# Clock_Updated_3_Nets.net
KiCad netlist of a schematic drawn in EAGLE
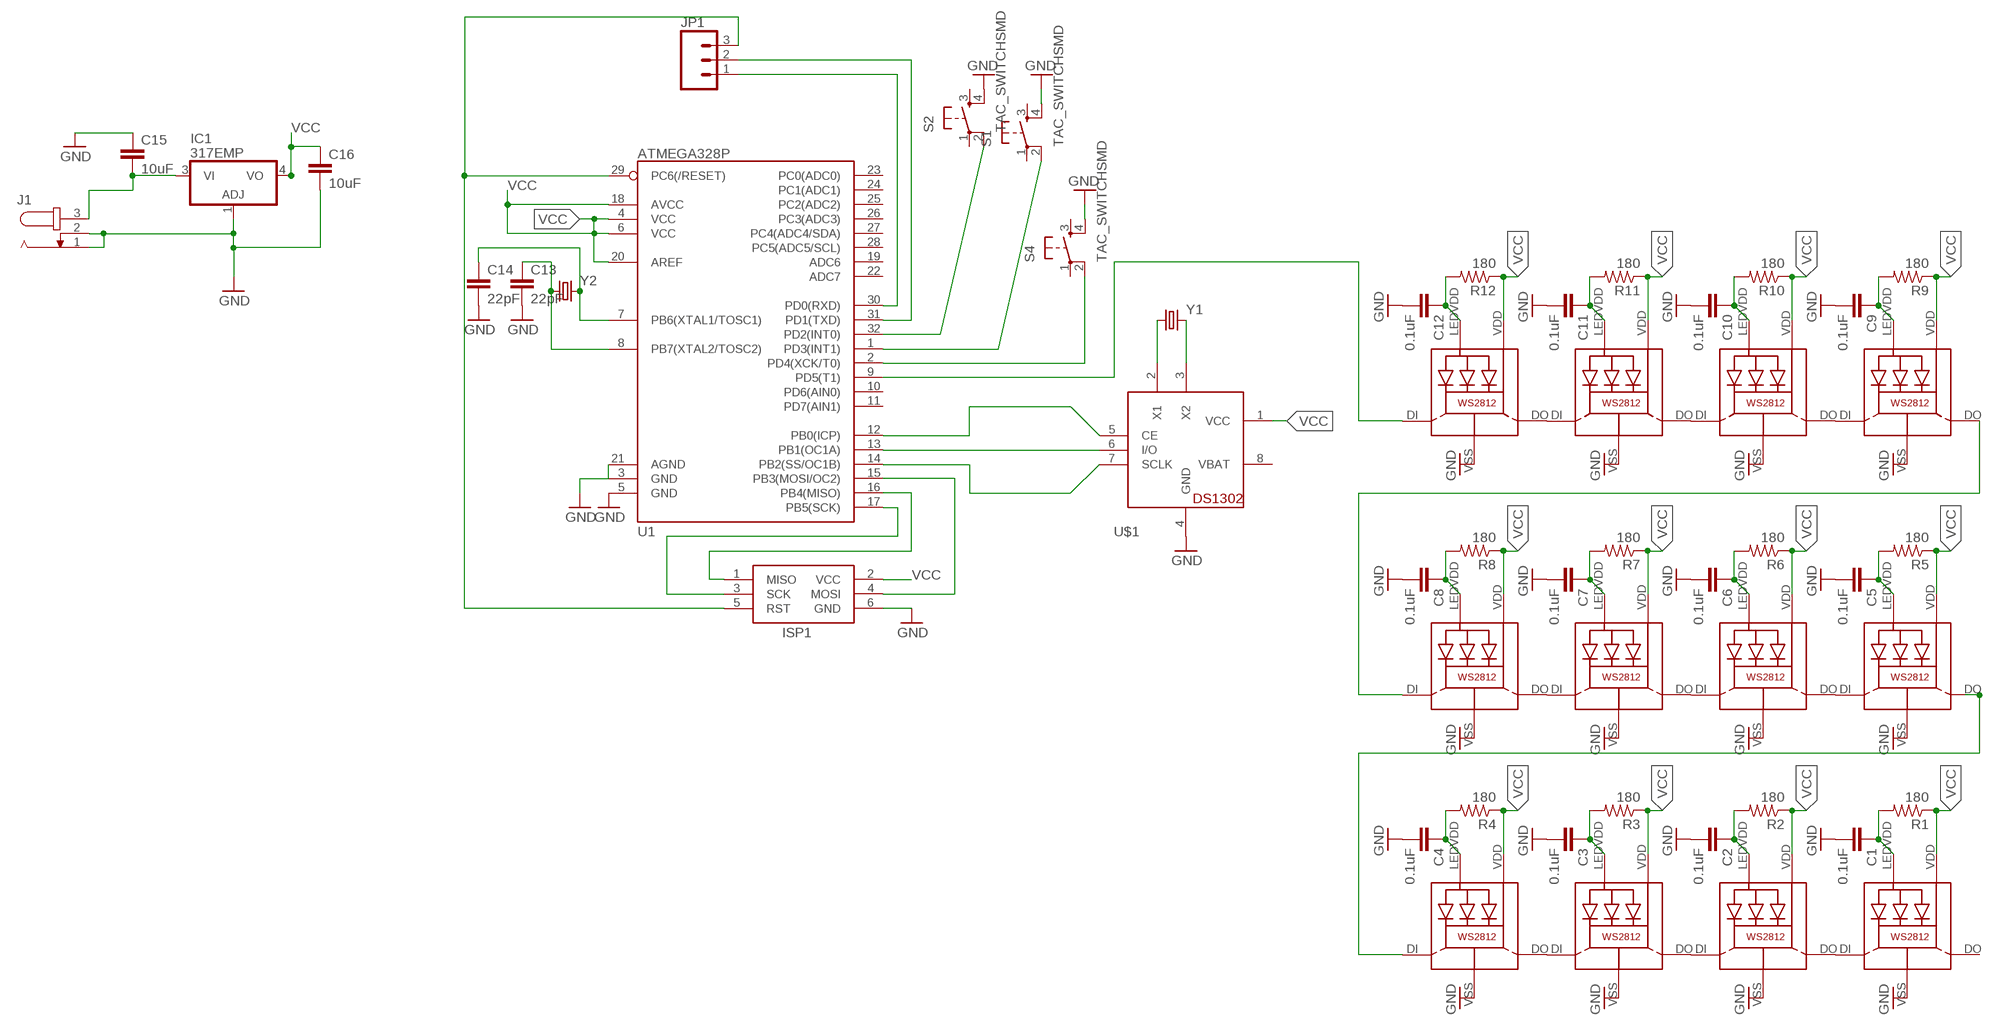
[diagram p0: schematic, sheet 1]

(export (version "E")
  (design (tool "Eeschema 10.0.6"))
  (components
    (comp (ref "C1")
      (value "0.1uF")
      (footprint "eagle-import:0603-CAP")
      (libsource (lib "eagle-import") (part "0.1UF-25V(+80/-20%)(0603)"))
    )
    (comp (ref "C2")
      (value "0.1uF")
      (footprint "eagle-import:0603-CAP")
      (libsource (lib "eagle-import") (part "0.1UF-25V(+80/-20%)(0603)"))
    )
    (comp (ref "C3")
      (value "0.1uF")
      (footprint "eagle-import:0603-CAP")
      (libsource (lib "eagle-import") (part "0.1UF-25V(+80/-20%)(0603)"))
    )
    (comp (ref "C4")
      (value "0.1uF")
      (footprint "eagle-import:0603-CAP")
      (libsource (lib "eagle-import") (part "0.1UF-25V(+80/-20%)(0603)"))
    )
    (comp (ref "C5")
      (value "0.1uF")
      (footprint "eagle-import:0603-CAP")
      (libsource (lib "eagle-import") (part "0.1UF-25V(+80/-20%)(0603)"))
    )
    (comp (ref "C6")
      (value "0.1uF")
      (footprint "eagle-import:0603-CAP")
      (libsource (lib "eagle-import") (part "0.1UF-25V(+80/-20%)(0603)"))
    )
    (comp (ref "C7")
      (value "0.1uF")
      (footprint "eagle-import:0603-CAP")
      (libsource (lib "eagle-import") (part "0.1UF-25V(+80/-20%)(0603)"))
    )
    (comp (ref "C8")
      (value "0.1uF")
      (footprint "eagle-import:0603-CAP")
      (libsource (lib "eagle-import") (part "0.1UF-25V(+80/-20%)(0603)"))
    )
    (comp (ref "C9")
      (value "0.1uF")
      (footprint "eagle-import:0603-CAP")
      (libsource (lib "eagle-import") (part "0.1UF-25V(+80/-20%)(0603)"))
    )
    (comp (ref "C10")
      (value "0.1uF")
      (footprint "eagle-import:0603-CAP")
      (libsource (lib "eagle-import") (part "0.1UF-25V(+80/-20%)(0603)"))
    )
    (comp (ref "C11")
      (value "0.1uF")
      (footprint "eagle-import:0603-CAP")
      (libsource (lib "eagle-import") (part "0.1UF-25V(+80/-20%)(0603)"))
    )
    (comp (ref "C12")
      (value "0.1uF")
      (footprint "eagle-import:0603-CAP")
      (libsource (lib "eagle-import") (part "0.1UF-25V(+80/-20%)(0603)"))
    )
    (comp (ref "C13")
      (value "22pF")
      (footprint "eagle-import:0603-CAP")
      (libsource (lib "eagle-import") (part "22PF-50V-5%(0603)"))
    )
    (comp (ref "C14")
      (value "22pF")
      (footprint "eagle-import:0603-CAP")
      (libsource (lib "eagle-import") (part "22PF-50V-5%(0603)"))
    )
    (comp (ref "C15")
      (value "10uF")
      (footprint "eagle-import:1206")
      (libsource (lib "eagle-import") (part "10UF-6.3V-20%(1206)"))
    )
    (comp (ref "C16")
      (value "10uF")
      (footprint "eagle-import:1206")
      (libsource (lib "eagle-import") (part "10UF-6.3V-20%(1206)"))
    )
    (comp (ref "IC1")
      (value "317EMP")
      (footprint "eagle-import:SOT223")
      (libsource (lib "eagle-import") (part "317EMP"))
    )
    (comp (ref "ISP1")
      (value "AVRISP-6")
      (footprint "eagle-import:AVRISP")
      (libsource (lib "eagle-import") (part "AVRISP-6"))
    )
    (comp (ref "J1")
      (value "JACK-PLUG0")
      (footprint "eagle-import:SPC4077")
      (libsource (lib "eagle-import") (part "JACK-PLUG0"))
    )
    (comp (ref "JP1")
      (value "M03JST-PTH-VERT")
      (footprint "eagle-import:JST-3-PTH-VERT")
      (libsource (lib "eagle-import") (part "M03JST-PTH-VERT"))
    )
    (comp (ref "LED1")
      (value "WS2812")
      (footprint "eagle-import:WS2812")
      (libsource (lib "eagle-import") (part "WS2812"))
    )
    (comp (ref "LED2")
      (value "WS2812")
      (footprint "eagle-import:WS2812")
      (libsource (lib "eagle-import") (part "WS2812"))
    )
    (comp (ref "LED3")
      (value "WS2812")
      (footprint "eagle-import:WS2812")
      (libsource (lib "eagle-import") (part "WS2812"))
    )
    (comp (ref "LED4")
      (value "WS2812")
      (footprint "eagle-import:WS2812")
      (libsource (lib "eagle-import") (part "WS2812"))
    )
    (comp (ref "LED5")
      (value "WS2812")
      (footprint "eagle-import:WS2812")
      (libsource (lib "eagle-import") (part "WS2812"))
    )
    (comp (ref "LED6")
      (value "WS2812")
      (footprint "eagle-import:WS2812")
      (libsource (lib "eagle-import") (part "WS2812"))
    )
    (comp (ref "LED7")
      (value "WS2812")
      (footprint "eagle-import:WS2812")
      (libsource (lib "eagle-import") (part "WS2812"))
    )
    (comp (ref "LED8")
      (value "WS2812")
      (footprint "eagle-import:WS2812")
      (libsource (lib "eagle-import") (part "WS2812"))
    )
    (comp (ref "LED9")
      (value "WS2812")
      (footprint "eagle-import:WS2812")
      (libsource (lib "eagle-import") (part "WS2812"))
    )
    (comp (ref "LED10")
      (value "WS2812")
      (footprint "eagle-import:WS2812")
      (libsource (lib "eagle-import") (part "WS2812"))
    )
    (comp (ref "LED11")
      (value "WS2812")
      (footprint "eagle-import:WS2812")
      (libsource (lib "eagle-import") (part "WS2812"))
    )
    (comp (ref "LED12")
      (value "WS2812")
      (footprint "eagle-import:WS2812")
      (libsource (lib "eagle-import") (part "WS2812"))
    )
    (comp (ref "R1")
      (value "180")
      (footprint "eagle-import:0603-RES")
      (libsource (lib "eagle-import") (part "180OHM1/10W1%(0603)"))
    )
    (comp (ref "R2")
      (value "180")
      (footprint "eagle-import:0603-RES")
      (libsource (lib "eagle-import") (part "180OHM1/10W1%(0603)"))
    )
    (comp (ref "R3")
      (value "180")
      (footprint "eagle-import:0603-RES")
      (libsource (lib "eagle-import") (part "180OHM1/10W1%(0603)"))
    )
    (comp (ref "R4")
      (value "180")
      (footprint "eagle-import:0603-RES")
      (libsource (lib "eagle-import") (part "180OHM1/10W1%(0603)"))
    )
    (comp (ref "R5")
      (value "180")
      (footprint "eagle-import:0603-RES")
      (libsource (lib "eagle-import") (part "180OHM1/10W1%(0603)"))
    )
    (comp (ref "R6")
      (value "180")
      (footprint "eagle-import:0603-RES")
      (libsource (lib "eagle-import") (part "180OHM1/10W1%(0603)"))
    )
    (comp (ref "R7")
      (value "180")
      (footprint "eagle-import:0603-RES")
      (libsource (lib "eagle-import") (part "180OHM1/10W1%(0603)"))
    )
    (comp (ref "R8")
      (value "180")
      (footprint "eagle-import:0603-RES")
      (libsource (lib "eagle-import") (part "180OHM1/10W1%(0603)"))
    )
    (comp (ref "R9")
      (value "180")
      (footprint "eagle-import:0603-RES")
      (libsource (lib "eagle-import") (part "180OHM1/10W1%(0603)"))
    )
    (comp (ref "R10")
      (value "180")
      (footprint "eagle-import:0603-RES")
      (libsource (lib "eagle-import") (part "180OHM1/10W1%(0603)"))
    )
    (comp (ref "R11")
      (value "180")
      (footprint "eagle-import:0603-RES")
      (libsource (lib "eagle-import") (part "180OHM1/10W1%(0603)"))
    )
    (comp (ref "R12")
      (value "180")
      (footprint "eagle-import:0603-RES")
      (libsource (lib "eagle-import") (part "180OHM1/10W1%(0603)"))
    )
    (comp (ref "S1")
      (value "TAC_SWITCHSMD")
      (footprint "eagle-import:TACTILE-SWITCH-SMD")
      (libsource (lib "eagle-import") (part "TAC_SWITCHSMD"))
    )
    (comp (ref "S2")
      (value "TAC_SWITCHSMD")
      (footprint "eagle-import:TACTILE-SWITCH-SMD")
      (libsource (lib "eagle-import") (part "TAC_SWITCHSMD"))
    )
    (comp (ref "S4")
      (value "TAC_SWITCHSMD")
      (footprint "eagle-import:TACTILE-SWITCH-SMD")
      (libsource (lib "eagle-import") (part "TAC_SWITCHSMD"))
    )
    (comp (ref "U$1")
      (value "DS1302")
      (footprint "eagle-import:DIL08-ROUND")
      (libsource (lib "eagle-import") (part "DS1302"))
    )
    (comp (ref "U1")
      (value "ATMEGA328P")
      (footprint "eagle-import:TQFP32-08")
      (libsource (lib "eagle-import") (part "ATMEGA328_SMT"))
    )
    (comp (ref "Y1")
      (value "CRYSTALTC38H")
      (footprint "eagle-import:TC38H")
      (libsource (lib "eagle-import") (part "CRYSTALTC38H"))
    )
    (comp (ref "Y2")
      (value "CRYSTALSMD")
      (footprint "eagle-import:HC49UP")
      (libsource (lib "eagle-import") (part "CRYSTALSMD"))
    )
  )
  (nets
    (net (code "1") (name "/VBAT") (class "Default")
      (node (ref "U$1") (pin "8") (pinfunction "VBAT_8") (pintype "power_in"))
    )
    (net (code "2") (name "GND") (class "Default")
      (node (ref "C1") (pin "2") (pinfunction "2_2") (pintype "passive"))
      (node (ref "C10") (pin "2") (pinfunction "2_2") (pintype "passive"))
      (node (ref "C11") (pin "2") (pinfunction "2_2") (pintype "passive"))
      (node (ref "C12") (pin "2") (pinfunction "2_2") (pintype "passive"))
      (node (ref "C13") (pin "2") (pinfunction "2_2") (pintype "passive"))
      (node (ref "C14") (pin "2") (pinfunction "2_2") (pintype "passive"))
      (node (ref "C15") (pin "1") (pinfunction "1_1") (pintype "passive"))
      (node (ref "C16") (pin "2") (pinfunction "2_2") (pintype "passive"))
      (node (ref "C2") (pin "2") (pinfunction "2_2") (pintype "passive"))
      (node (ref "C3") (pin "2") (pinfunction "2_2") (pintype "passive"))
      (node (ref "C4") (pin "2") (pinfunction "2_2") (pintype "passive"))
      (node (ref "C5") (pin "2") (pinfunction "2_2") (pintype "passive"))
      (node (ref "C6") (pin "2") (pinfunction "2_2") (pintype "passive"))
      (node (ref "C7") (pin "2") (pinfunction "2_2") (pintype "passive"))
      (node (ref "C8") (pin "2") (pinfunction "2_2") (pintype "passive"))
      (node (ref "C9") (pin "2") (pinfunction "2_2") (pintype "passive"))
      (node (ref "IC1") (pin "1") (pinfunction "ADJ_1") (pintype "input"))
      (node (ref "ISP1") (pin "6") (pinfunction "GND_6") (pintype "power_in"))
      (node (ref "J1") (pin "1") (pinfunction "1_1") (pintype "passive"))
      (node (ref "J1") (pin "2") (pinfunction "2_2") (pintype "passive"))
      (node (ref "LED1") (pin "VSS") (pinfunction "GND_VSS") (pintype "power_in"))
      (node (ref "LED10") (pin "VSS") (pinfunction "GND_VSS") (pintype "power_in"))
      (node (ref "LED11") (pin "VSS") (pinfunction "GND_VSS") (pintype "power_in"))
      (node (ref "LED12") (pin "VSS") (pinfunction "GND_VSS") (pintype "power_in"))
      (node (ref "LED2") (pin "VSS") (pinfunction "GND_VSS") (pintype "power_in"))
      (node (ref "LED3") (pin "VSS") (pinfunction "GND_VSS") (pintype "power_in"))
      (node (ref "LED4") (pin "VSS") (pinfunction "GND_VSS") (pintype "power_in"))
      (node (ref "LED5") (pin "VSS") (pinfunction "GND_VSS") (pintype "power_in"))
      (node (ref "LED6") (pin "VSS") (pinfunction "GND_VSS") (pintype "power_in"))
      (node (ref "LED7") (pin "VSS") (pinfunction "GND_VSS") (pintype "power_in"))
      (node (ref "LED8") (pin "VSS") (pinfunction "GND_VSS") (pintype "power_in"))
      (node (ref "LED9") (pin "VSS") (pinfunction "GND_VSS") (pintype "power_in"))
      (node (ref "S1") (pin "4") (pinfunction "4_4") (pintype "passive"))
      (node (ref "S2") (pin "4") (pinfunction "4_4") (pintype "passive"))
      (node (ref "S4") (pin "4") (pinfunction "4_4") (pintype "passive"))
      (node (ref "U$1") (pin "4") (pinfunction "GND_4") (pintype "power_in"))
      (node (ref "U1") (pin "21") (pinfunction "AGND_21") (pintype "bidirectional"))
      (node (ref "U1") (pin "3") (pinfunction "GND_3") (pintype "bidirectional"))
      (node (ref "U1") (pin "5") (pinfunction "GND_5") (pintype "bidirectional"))
    )
    (net (code "3") (name "Net-(C1-Pad1)") (class "Default")
      (node (ref "C1") (pin "1") (pinfunction "1_1") (pintype "passive"))
      (node (ref "LED1") (pin "LEDVDD") (pinfunction "LEDVDD_LEDVDD") (pintype "power_in"))
      (node (ref "R1") (pin "2") (pinfunction "2_2") (pintype "passive"))
    )
    (net (code "4") (name "Net-(C2-Pad1)") (class "Default")
      (node (ref "C2") (pin "1") (pinfunction "1_1") (pintype "passive"))
      (node (ref "LED2") (pin "LEDVDD") (pinfunction "LEDVDD_LEDVDD") (pintype "power_in"))
      (node (ref "R2") (pin "2") (pinfunction "2_2") (pintype "passive"))
    )
    (net (code "5") (name "Net-(C3-Pad1)") (class "Default")
      (node (ref "C3") (pin "1") (pinfunction "1_1") (pintype "passive"))
      (node (ref "LED3") (pin "LEDVDD") (pinfunction "LEDVDD_LEDVDD") (pintype "power_in"))
      (node (ref "R3") (pin "2") (pinfunction "2_2") (pintype "passive"))
    )
    (net (code "6") (name "Net-(C4-Pad1)") (class "Default")
      (node (ref "C4") (pin "1") (pinfunction "1_1") (pintype "passive"))
      (node (ref "LED4") (pin "LEDVDD") (pinfunction "LEDVDD_LEDVDD") (pintype "power_in"))
      (node (ref "R4") (pin "2") (pinfunction "2_2") (pintype "passive"))
    )
    (net (code "7") (name "Net-(C5-Pad1)") (class "Default")
      (node (ref "C5") (pin "1") (pinfunction "1_1") (pintype "passive"))
      (node (ref "LED5") (pin "LEDVDD") (pinfunction "LEDVDD_LEDVDD") (pintype "power_in"))
      (node (ref "R5") (pin "2") (pinfunction "2_2") (pintype "passive"))
    )
    (net (code "8") (name "Net-(C6-Pad1)") (class "Default")
      (node (ref "C6") (pin "1") (pinfunction "1_1") (pintype "passive"))
      (node (ref "LED6") (pin "LEDVDD") (pinfunction "LEDVDD_LEDVDD") (pintype "power_in"))
      (node (ref "R6") (pin "2") (pinfunction "2_2") (pintype "passive"))
    )
    (net (code "9") (name "Net-(C7-Pad1)") (class "Default")
      (node (ref "C7") (pin "1") (pinfunction "1_1") (pintype "passive"))
      (node (ref "LED7") (pin "LEDVDD") (pinfunction "LEDVDD_LEDVDD") (pintype "power_in"))
      (node (ref "R7") (pin "2") (pinfunction "2_2") (pintype "passive"))
    )
    (net (code "10") (name "Net-(C8-Pad1)") (class "Default")
      (node (ref "C8") (pin "1") (pinfunction "1_1") (pintype "passive"))
      (node (ref "LED8") (pin "LEDVDD") (pinfunction "LEDVDD_LEDVDD") (pintype "power_in"))
      (node (ref "R8") (pin "2") (pinfunction "2_2") (pintype "passive"))
    )
    (net (code "11") (name "Net-(C9-Pad1)") (class "Default")
      (node (ref "C9") (pin "1") (pinfunction "1_1") (pintype "passive"))
      (node (ref "LED9") (pin "LEDVDD") (pinfunction "LEDVDD_LEDVDD") (pintype "power_in"))
      (node (ref "R9") (pin "2") (pinfunction "2_2") (pintype "passive"))
    )
    (net (code "12") (name "Net-(C10-Pad1)") (class "Default")
      (node (ref "C10") (pin "1") (pinfunction "1_1") (pintype "passive"))
      (node (ref "LED10") (pin "LEDVDD") (pinfunction "LEDVDD_LEDVDD") (pintype "power_in"))
      (node (ref "R10") (pin "2") (pinfunction "2_2") (pintype "passive"))
    )
    (net (code "13") (name "Net-(C11-Pad1)") (class "Default")
      (node (ref "C11") (pin "1") (pinfunction "1_1") (pintype "passive"))
      (node (ref "LED11") (pin "LEDVDD") (pinfunction "LEDVDD_LEDVDD") (pintype "power_in"))
      (node (ref "R11") (pin "2") (pinfunction "2_2") (pintype "passive"))
    )
    (net (code "14") (name "Net-(C12-Pad1)") (class "Default")
      (node (ref "C12") (pin "1") (pinfunction "1_1") (pintype "passive"))
      (node (ref "LED12") (pin "LEDVDD") (pinfunction "LEDVDD_LEDVDD") (pintype "power_in"))
      (node (ref "R12") (pin "2") (pinfunction "2_2") (pintype "passive"))
    )
    (net (code "15") (name "Net-(IC1-VI)") (class "Default")
      (node (ref "C15") (pin "2") (pinfunction "2_2") (pintype "passive"))
      (node (ref "IC1") (pin "3") (pinfunction "VI_3") (pintype "input"))
      (node (ref "J1") (pin "3") (pinfunction "3_3") (pintype "passive"))
    )
    (net (code "16") (name "Net-(ISP1-MISO)") (class "Default")
      (node (ref "ISP1") (pin "1") (pinfunction "MISO_1") (pintype "input"))
      (node (ref "U1") (pin "16") (pinfunction "PB4(MISO)_16") (pintype "bidirectional"))
    )
    (net (code "17") (name "Net-(ISP1-MOSI)") (class "Default")
      (node (ref "ISP1") (pin "4") (pinfunction "MOSI_4") (pintype "output"))
      (node (ref "U1") (pin "15") (pinfunction "PB3(MOSI/OC2)_15") (pintype "bidirectional"))
    )
    (net (code "18") (name "Net-(ISP1-RST)") (class "Default")
      (node (ref "ISP1") (pin "5") (pinfunction "RST_5") (pintype "output"))
      (node (ref "JP1") (pin "3") (pinfunction "3_3") (pintype "passive"))
      (node (ref "U1") (pin "29") (pinfunction "PC6(/RESET)_29") (pintype "bidirectional"))
    )
    (net (code "19") (name "Net-(ISP1-SCK)") (class "Default")
      (node (ref "ISP1") (pin "3") (pinfunction "SCK_3") (pintype "output"))
      (node (ref "U1") (pin "17") (pinfunction "PB5(SCK)_17") (pintype "bidirectional"))
    )
    (net (code "20") (name "Net-(LED1-PadDI)") (class "Default")
      (node (ref "LED1") (pin "DI") (pinfunction "DI_DI") (pintype "input"))
      (node (ref "LED2") (pin "DO") (pinfunction "DO_DO") (pintype "output"))
    )
    (net (code "21") (name "Net-(LED2-PadDI)") (class "Default")
      (node (ref "LED2") (pin "DI") (pinfunction "DI_DI") (pintype "input"))
      (node (ref "LED3") (pin "DO") (pinfunction "DO_DO") (pintype "output"))
    )
    (net (code "22") (name "Net-(LED3-PadDI)") (class "Default")
      (node (ref "LED3") (pin "DI") (pinfunction "DI_DI") (pintype "input"))
      (node (ref "LED4") (pin "DO") (pinfunction "DO_DO") (pintype "output"))
    )
    (net (code "23") (name "Net-(LED4-PadDI)") (class "Default")
      (node (ref "LED4") (pin "DI") (pinfunction "DI_DI") (pintype "input"))
      (node (ref "LED5") (pin "DO") (pinfunction "DO_DO") (pintype "output"))
    )
    (net (code "24") (name "Net-(LED5-PadDI)") (class "Default")
      (node (ref "LED5") (pin "DI") (pinfunction "DI_DI") (pintype "input"))
      (node (ref "LED6") (pin "DO") (pinfunction "DO_DO") (pintype "output"))
    )
    (net (code "25") (name "Net-(LED6-PadDI)") (class "Default")
      (node (ref "LED6") (pin "DI") (pinfunction "DI_DI") (pintype "input"))
      (node (ref "LED7") (pin "DO") (pinfunction "DO_DO") (pintype "output"))
    )
    (net (code "26") (name "Net-(LED7-PadDI)") (class "Default")
      (node (ref "LED7") (pin "DI") (pinfunction "DI_DI") (pintype "input"))
      (node (ref "LED8") (pin "DO") (pinfunction "DO_DO") (pintype "output"))
    )
    (net (code "27") (name "Net-(LED8-PadDI)") (class "Default")
      (node (ref "LED8") (pin "DI") (pinfunction "DI_DI") (pintype "input"))
      (node (ref "LED9") (pin "DO") (pinfunction "DO_DO") (pintype "output"))
    )
    (net (code "28") (name "Net-(LED10-PadDI)") (class "Default")
      (node (ref "LED10") (pin "DI") (pinfunction "DI_DI") (pintype "input"))
      (node (ref "LED11") (pin "DO") (pinfunction "DO_DO") (pintype "output"))
    )
    (net (code "29") (name "Net-(LED10-PadDO)") (class "Default")
      (node (ref "LED10") (pin "DO") (pinfunction "DO_DO") (pintype "output"))
      (node (ref "LED9") (pin "DI") (pinfunction "DI_DI") (pintype "input"))
    )
    (net (code "30") (name "Net-(LED11-PadDI)") (class "Default")
      (node (ref "LED11") (pin "DI") (pinfunction "DI_DI") (pintype "input"))
      (node (ref "LED12") (pin "DO") (pinfunction "DO_DO") (pintype "output"))
    )
    (net (code "31") (name "Net-(U$1-CE)") (class "Default")
      (node (ref "U$1") (pin "5") (pinfunction "CE_5") (pintype "input"))
      (node (ref "U1") (pin "12") (pinfunction "PB0(ICP)_12") (pintype "bidirectional"))
    )
    (net (code "32") (name "Net-(U$1-I{slash}O)") (class "Default")
      (node (ref "U$1") (pin "6") (pinfunction "I/O_6") (pintype "bidirectional"))
      (node (ref "U1") (pin "13") (pinfunction "PB1(OC1A)_13") (pintype "bidirectional"))
    )
    (net (code "33") (name "Net-(U$1-SCLK)") (class "Default")
      (node (ref "U$1") (pin "7") (pinfunction "SCLK_7") (pintype "input"))
      (node (ref "U1") (pin "14") (pinfunction "PB2(SS/OC1B)_14") (pintype "bidirectional"))
    )
    (net (code "34") (name "Net-(U$1-X1)") (class "Default")
      (node (ref "U$1") (pin "2") (pinfunction "X1_2") (pintype "passive"))
      (node (ref "Y1") (pin "1") (pinfunction "1_1") (pintype "passive"))
    )
    (net (code "35") (name "Net-(U$1-X2)") (class "Default")
      (node (ref "U$1") (pin "3") (pinfunction "X2_3") (pintype "passive"))
      (node (ref "Y1") (pin "2") (pinfunction "2_2") (pintype "passive"))
    )
    (net (code "36") (name "Net-(U1-PB6(XTAL1{slash}TOSC1))") (class "Default")
      (node (ref "C14") (pin "1") (pinfunction "1_1") (pintype "passive"))
      (node (ref "U1") (pin "7") (pinfunction "PB6(XTAL1/TOSC1)_7") (pintype "bidirectional"))
      (node (ref "Y2") (pin "2") (pinfunction "2_2") (pintype "passive"))
    )
    (net (code "37") (name "Net-(U1-PB7(XTAL2{slash}TOSC2))") (class "Default")
      (node (ref "C13") (pin "1") (pinfunction "1_1") (pintype "passive"))
      (node (ref "U1") (pin "8") (pinfunction "PB7(XTAL2/TOSC2)_8") (pintype "bidirectional"))
      (node (ref "Y2") (pin "1") (pinfunction "1_1") (pintype "passive"))
    )
    (net (code "38") (name "Net-(U1-PD0(RXD))") (class "Default")
      (node (ref "JP1") (pin "1") (pinfunction "1_1") (pintype "passive"))
      (node (ref "U1") (pin "30") (pinfunction "PD0(RXD)_30") (pintype "bidirectional"))
    )
    (net (code "39") (name "Net-(U1-PD1(TXD))") (class "Default")
      (node (ref "JP1") (pin "2") (pinfunction "2_2") (pintype "passive"))
      (node (ref "U1") (pin "31") (pinfunction "PD1(TXD)_31") (pintype "bidirectional"))
    )
    (net (code "40") (name "Net-(U1-PD2(INT0))") (class "Default")
      (node (ref "S2") (pin "2") (pinfunction "2_2") (pintype "passive"))
      (node (ref "U1") (pin "32") (pinfunction "PD2(INT0)_32") (pintype "bidirectional"))
    )
    (net (code "41") (name "Net-(U1-PD3(INT1))") (class "Default")
      (node (ref "S1") (pin "2") (pinfunction "2_2") (pintype "passive"))
      (node (ref "U1") (pin "1") (pinfunction "PD3(INT1)_1") (pintype "bidirectional"))
    )
    (net (code "42") (name "Net-(U1-PD4(XCK{slash}T0))") (class "Default")
      (node (ref "S4") (pin "2") (pinfunction "2_2") (pintype "passive"))
      (node (ref "U1") (pin "2") (pinfunction "PD4(XCK/T0)_2") (pintype "bidirectional"))
    )
    (net (code "43") (name "Net-(U1-PD5(T1))") (class "Default")
      (node (ref "LED12") (pin "DI") (pinfunction "DI_DI") (pintype "input"))
      (node (ref "U1") (pin "9") (pinfunction "PD5(T1)_9") (pintype "bidirectional"))
    )
    (net (code "44") (name "VCC") (class "Default")
      (node (ref "C16") (pin "1") (pinfunction "1_1") (pintype "passive"))
      (node (ref "IC1") (pin "4") (pinfunction "VO_4") (pintype "passive"))
      (node (ref "ISP1") (pin "2") (pinfunction "VCC_2") (pintype "power_in"))
      (node (ref "LED1") (pin "VDD") (pinfunction "VDD_VDD") (pintype "power_in"))
      (node (ref "LED10") (pin "VDD") (pinfunction "VDD_VDD") (pintype "power_in"))
      (node (ref "LED11") (pin "VDD") (pinfunction "VDD_VDD") (pintype "power_in"))
      (node (ref "LED12") (pin "VDD") (pinfunction "VDD_VDD") (pintype "power_in"))
      (node (ref "LED2") (pin "VDD") (pinfunction "VDD_VDD") (pintype "power_in"))
      (node (ref "LED3") (pin "VDD") (pinfunction "VDD_VDD") (pintype "power_in"))
      (node (ref "LED4") (pin "VDD") (pinfunction "VDD_VDD") (pintype "power_in"))
      (node (ref "LED5") (pin "VDD") (pinfunction "VDD_VDD") (pintype "power_in"))
      (node (ref "LED6") (pin "VDD") (pinfunction "VDD_VDD") (pintype "power_in"))
      (node (ref "LED7") (pin "VDD") (pinfunction "VDD_VDD") (pintype "power_in"))
      (node (ref "LED8") (pin "VDD") (pinfunction "VDD_VDD") (pintype "power_in"))
      (node (ref "LED9") (pin "VDD") (pinfunction "VDD_VDD") (pintype "power_in"))
      (node (ref "R1") (pin "1") (pinfunction "1_1") (pintype "passive"))
      (node (ref "R10") (pin "1") (pinfunction "1_1") (pintype "passive"))
      (node (ref "R11") (pin "1") (pinfunction "1_1") (pintype "passive"))
      (node (ref "R12") (pin "1") (pinfunction "1_1") (pintype "passive"))
      (node (ref "R2") (pin "1") (pinfunction "1_1") (pintype "passive"))
      (node (ref "R3") (pin "1") (pinfunction "1_1") (pintype "passive"))
      (node (ref "R4") (pin "1") (pinfunction "1_1") (pintype "passive"))
      (node (ref "R5") (pin "1") (pinfunction "1_1") (pintype "passive"))
      (node (ref "R6") (pin "1") (pinfunction "1_1") (pintype "passive"))
      (node (ref "R7") (pin "1") (pinfunction "1_1") (pintype "passive"))
      (node (ref "R8") (pin "1") (pinfunction "1_1") (pintype "passive"))
      (node (ref "R9") (pin "1") (pinfunction "1_1") (pintype "passive"))
      (node (ref "U$1") (pin "1") (pinfunction "VCC_1") (pintype "power_in"))
      (node (ref "U1") (pin "18") (pinfunction "AVCC_18") (pintype "bidirectional"))
      (node (ref "U1") (pin "20") (pinfunction "AREF_20") (pintype "bidirectional"))
      (node (ref "U1") (pin "4") (pinfunction "VCC_4") (pintype "bidirectional"))
      (node (ref "U1") (pin "6") (pinfunction "VCC_6") (pintype "bidirectional"))
    )
    (net (code "45") (name "unconnected-(LED1-PadDO)") (class "Default")
      (node (ref "LED1") (pin "DO") (pinfunction "DO_DO") (pintype "output"))
    )
    (net (code "46") (name "unconnected-(S1-Pad1)") (class "Default")
      (node (ref "S1") (pin "1") (pinfunction "1_1") (pintype "passive"))
    )
    (net (code "47") (name "unconnected-(S1-Pad3)") (class "Default")
      (node (ref "S1") (pin "3") (pinfunction "3_3") (pintype "passive"))
    )
    (net (code "48") (name "unconnected-(S2-Pad1)") (class "Default")
      (node (ref "S2") (pin "1") (pinfunction "1_1") (pintype "passive"))
    )
    (net (code "49") (name "unconnected-(S2-Pad3)") (class "Default")
      (node (ref "S2") (pin "3") (pinfunction "3_3") (pintype "passive"))
    )
    (net (code "50") (name "unconnected-(S4-Pad1)") (class "Default")
      (node (ref "S4") (pin "1") (pinfunction "1_1") (pintype "passive"))
    )
    (net (code "51") (name "unconnected-(S4-Pad3)") (class "Default")
      (node (ref "S4") (pin "3") (pinfunction "3_3") (pintype "passive"))
    )
    (net (code "52") (name "unconnected-(U1-ADC6-Pad19)") (class "Default")
      (node (ref "U1") (pin "19") (pinfunction "ADC6_19") (pintype "bidirectional"))
    )
    (net (code "53") (name "unconnected-(U1-ADC7-Pad22)") (class "Default")
      (node (ref "U1") (pin "22") (pinfunction "ADC7_22") (pintype "bidirectional"))
    )
    (net (code "54") (name "unconnected-(U1-PC0(ADC0)-Pad23)") (class "Default")
      (node (ref "U1") (pin "23") (pinfunction "PC0(ADC0)_23") (pintype "bidirectional"))
    )
    (net (code "55") (name "unconnected-(U1-PC1(ADC1)-Pad24)") (class "Default")
      (node (ref "U1") (pin "24") (pinfunction "PC1(ADC1)_24") (pintype "bidirectional"))
    )
    (net (code "56") (name "unconnected-(U1-PC2(ADC2)-Pad25)") (class "Default")
      (node (ref "U1") (pin "25") (pinfunction "PC2(ADC2)_25") (pintype "bidirectional"))
    )
    (net (code "57") (name "unconnected-(U1-PC3(ADC3)-Pad26)") (class "Default")
      (node (ref "U1") (pin "26") (pinfunction "PC3(ADC3)_26") (pintype "bidirectional"))
    )
    (net (code "58") (name "unconnected-(U1-PC4(ADC4{slash}SDA)-Pad27)") (class "Default")
      (node (ref "U1") (pin "27") (pinfunction "PC4(ADC4/SDA)_27") (pintype "bidirectional"))
    )
    (net (code "59") (name "unconnected-(U1-PC5(ADC5{slash}SCL)-Pad28)") (class "Default")
      (node (ref "U1") (pin "28") (pinfunction "PC5(ADC5/SCL)_28") (pintype "bidirectional"))
    )
    (net (code "60") (name "unconnected-(U1-PD6(AIN0)-Pad10)") (class "Default")
      (node (ref "U1") (pin "10") (pinfunction "PD6(AIN0)_10") (pintype "bidirectional"))
    )
    (net (code "61") (name "unconnected-(U1-PD7(AIN1)-Pad11)") (class "Default")
      (node (ref "U1") (pin "11") (pinfunction "PD7(AIN1)_11") (pintype "bidirectional"))
    )
  )
)
